# SensorMoteSMT_V1_1MCAD.net
KiCad netlist of a schematic drawn in EAGLE
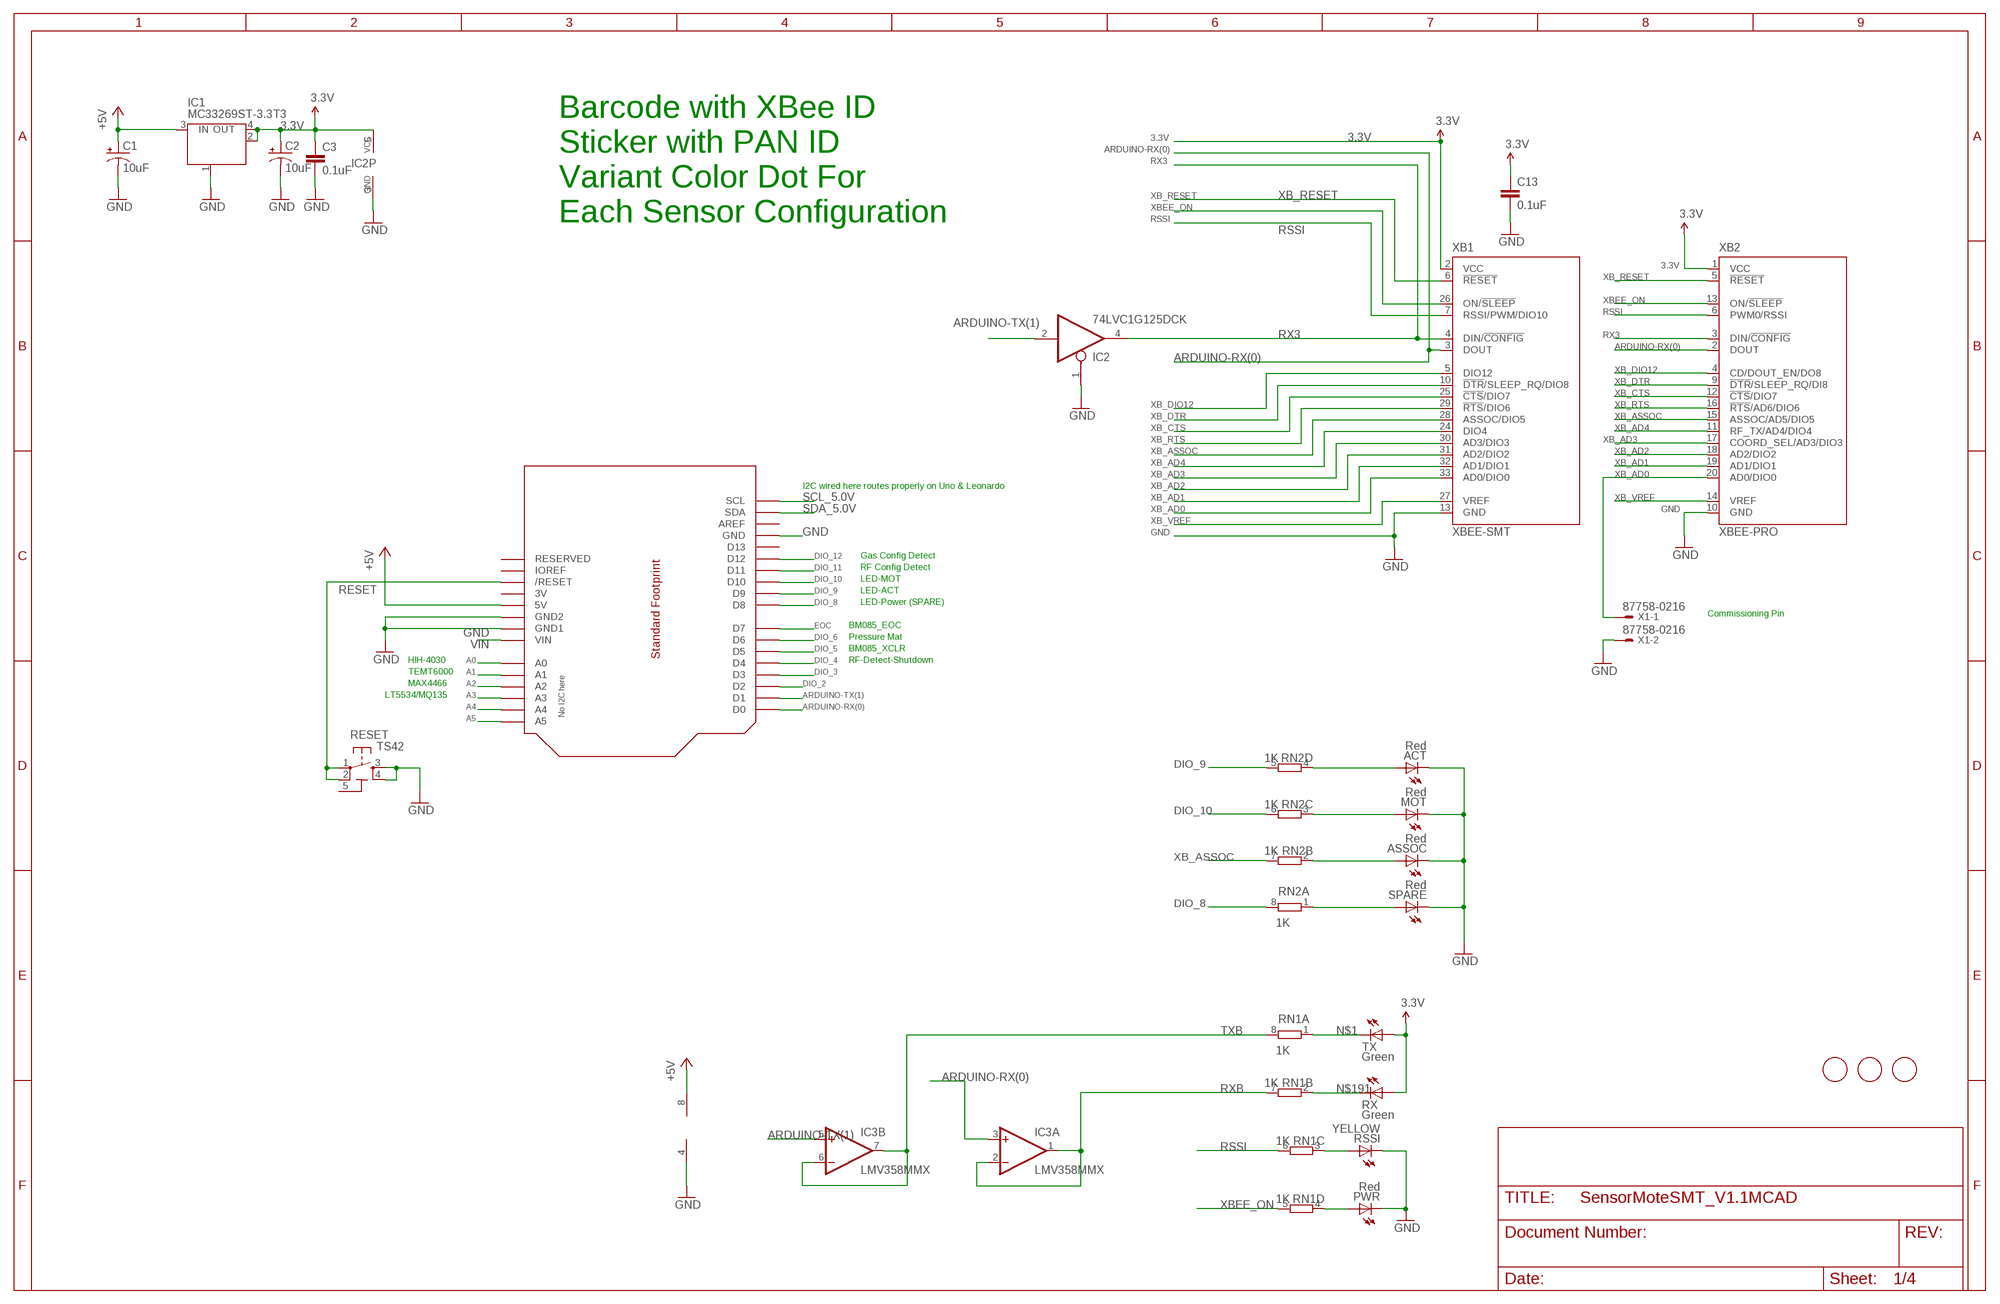
[diagram p0: schematic, sheet 1]
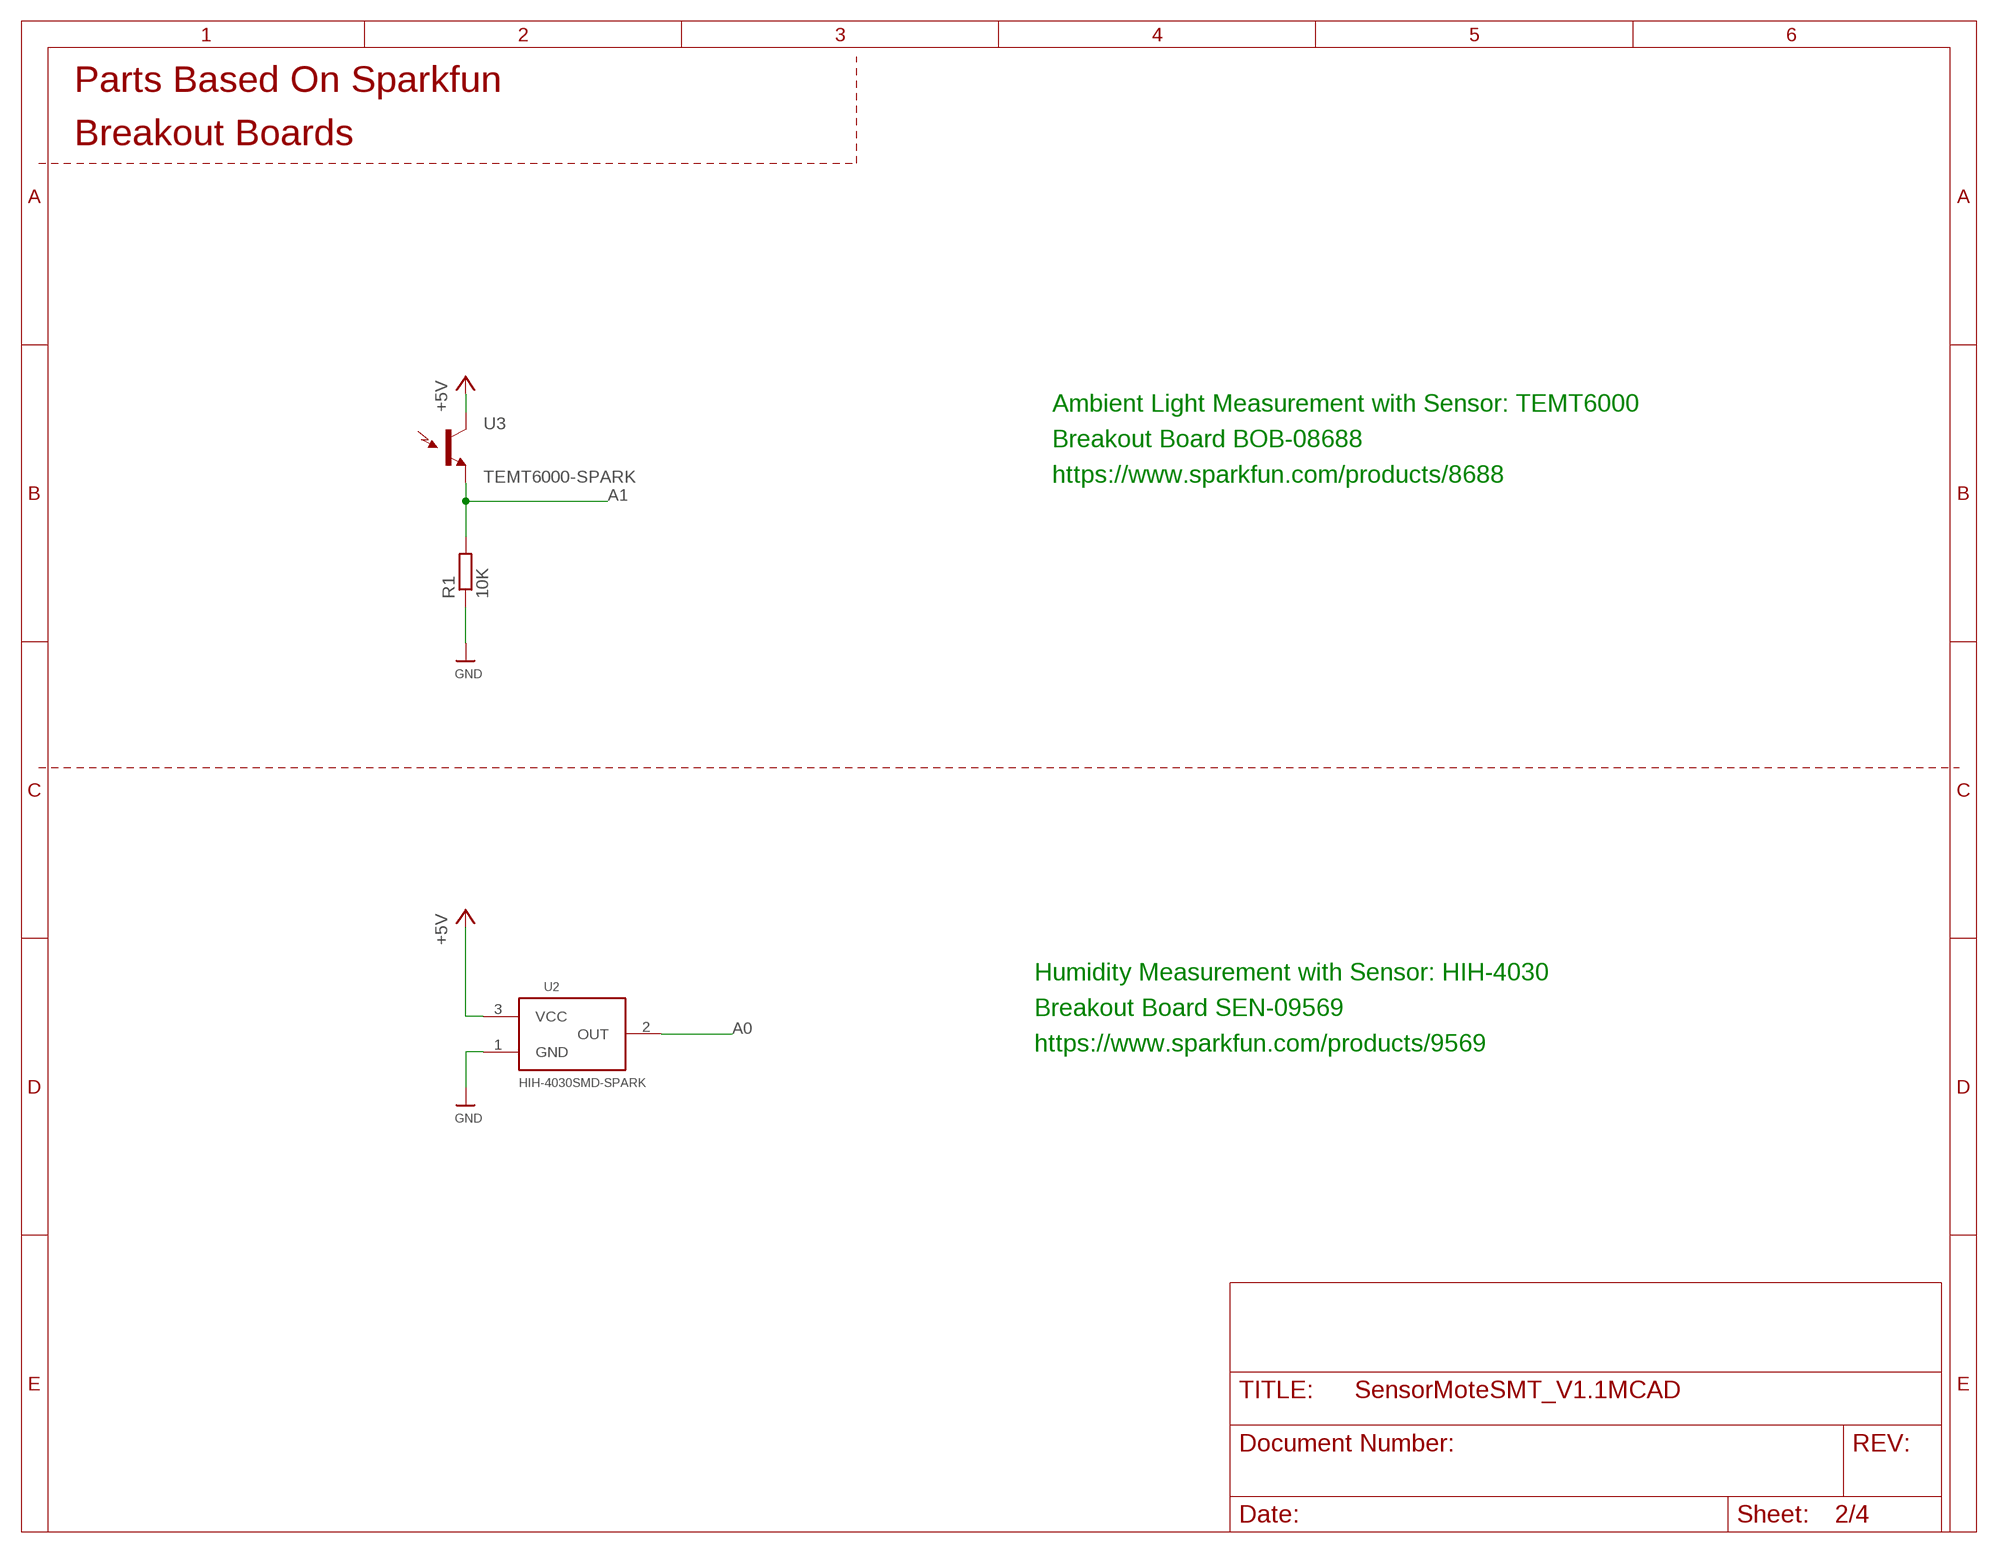
[diagram p1: schematic, sheet 2]
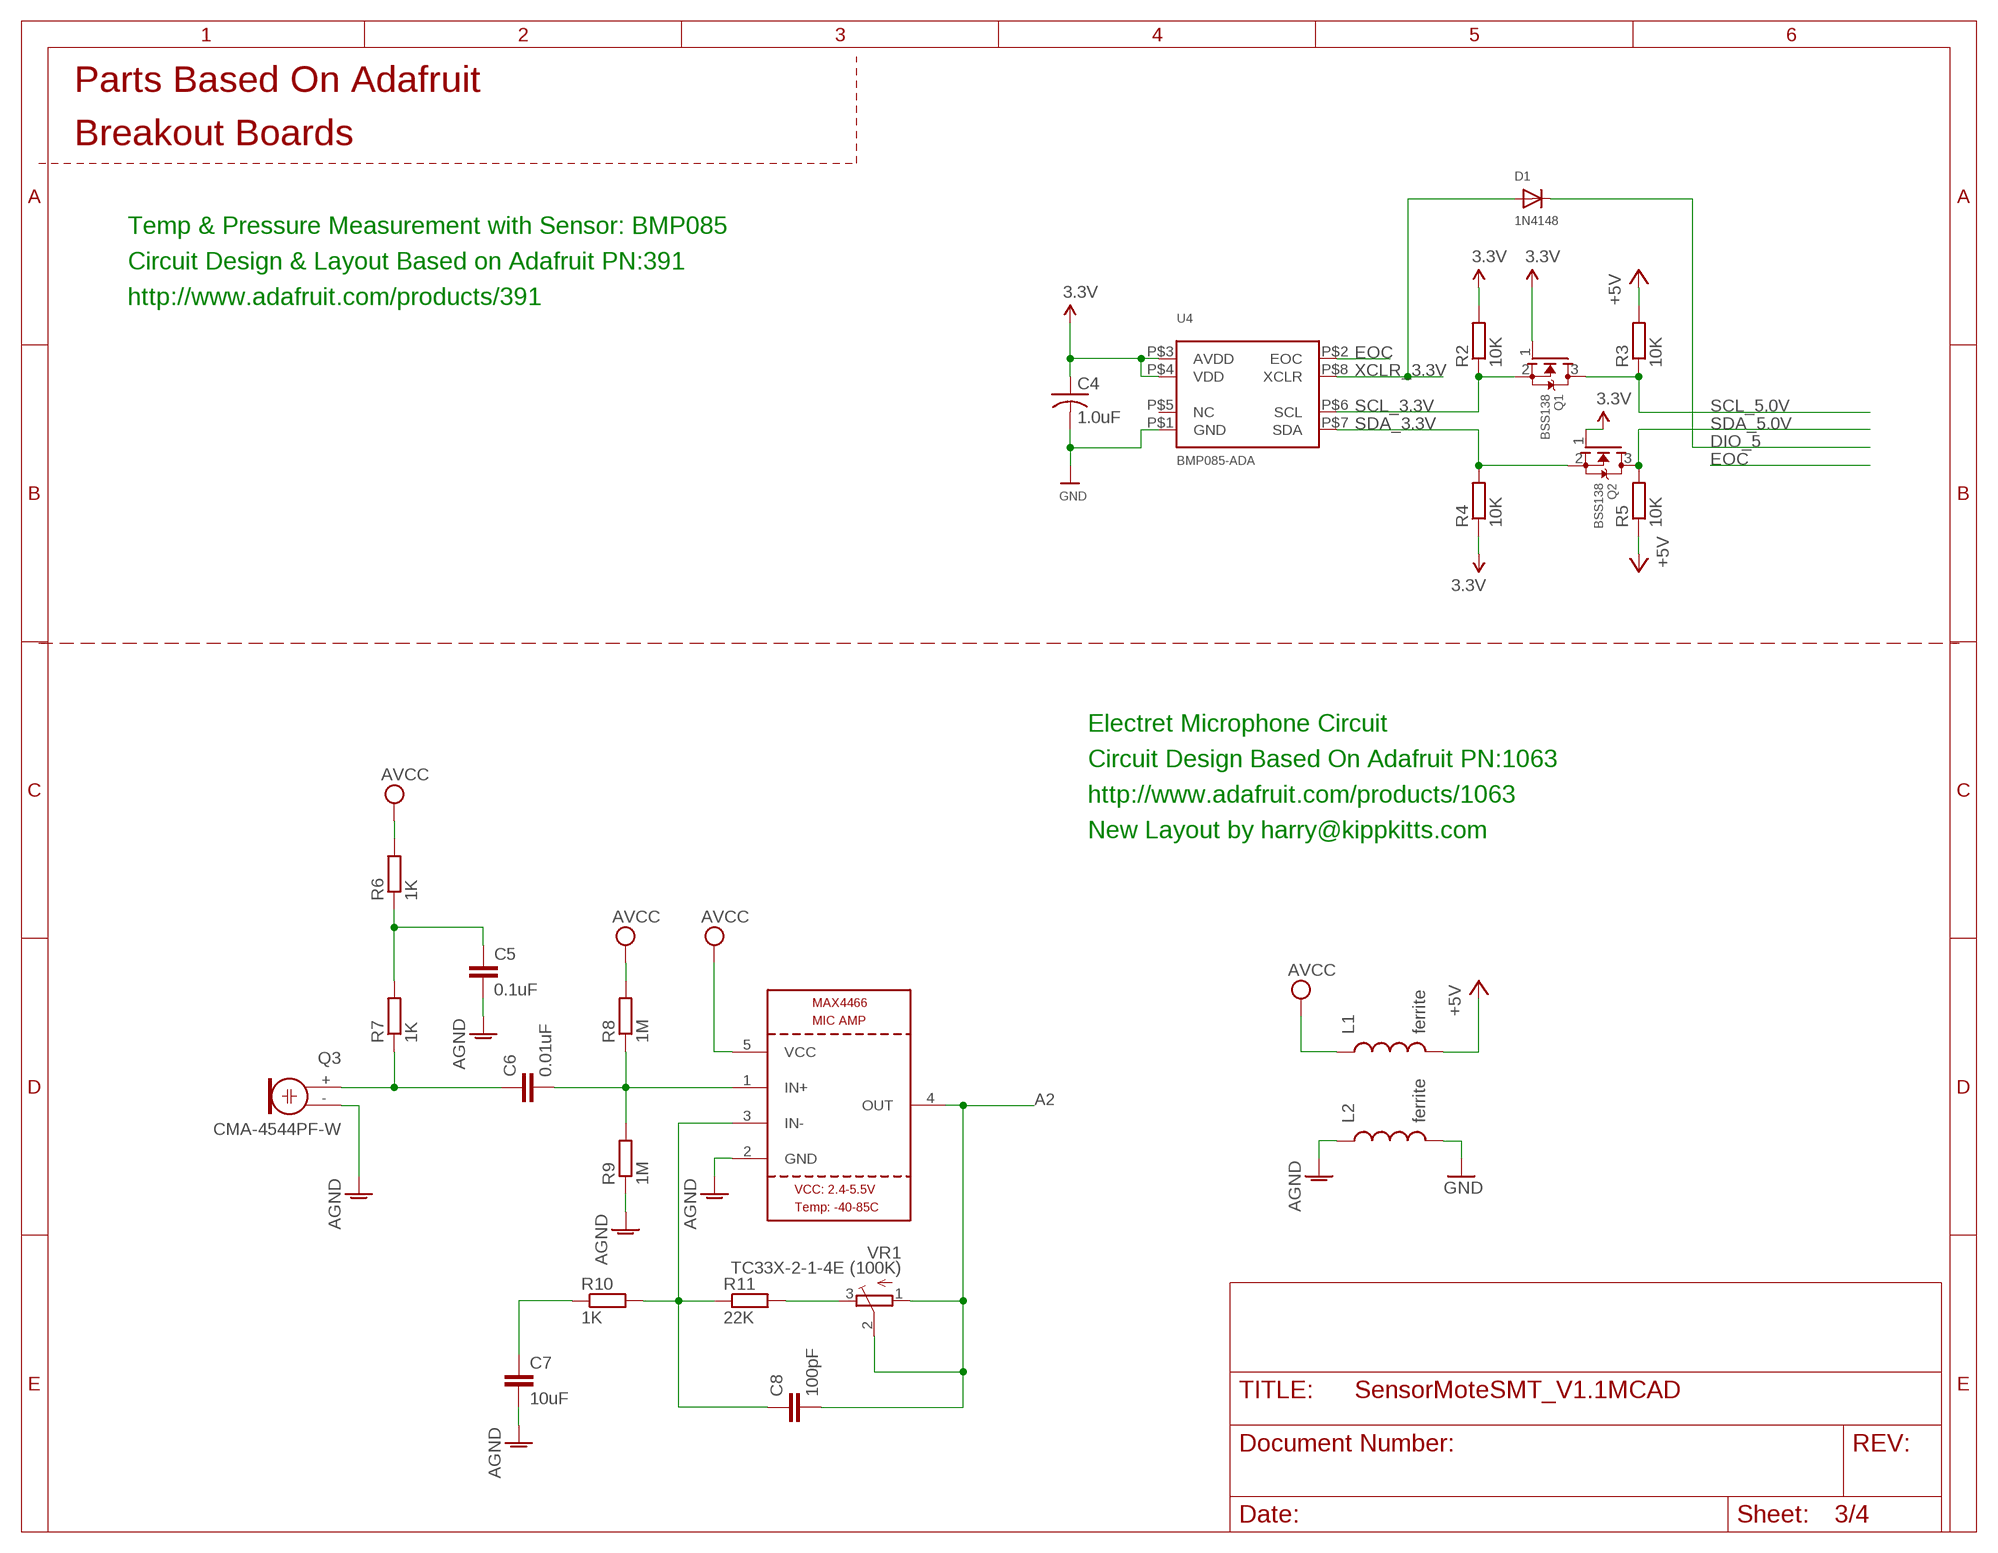
[diagram p2: schematic, sheet 3]
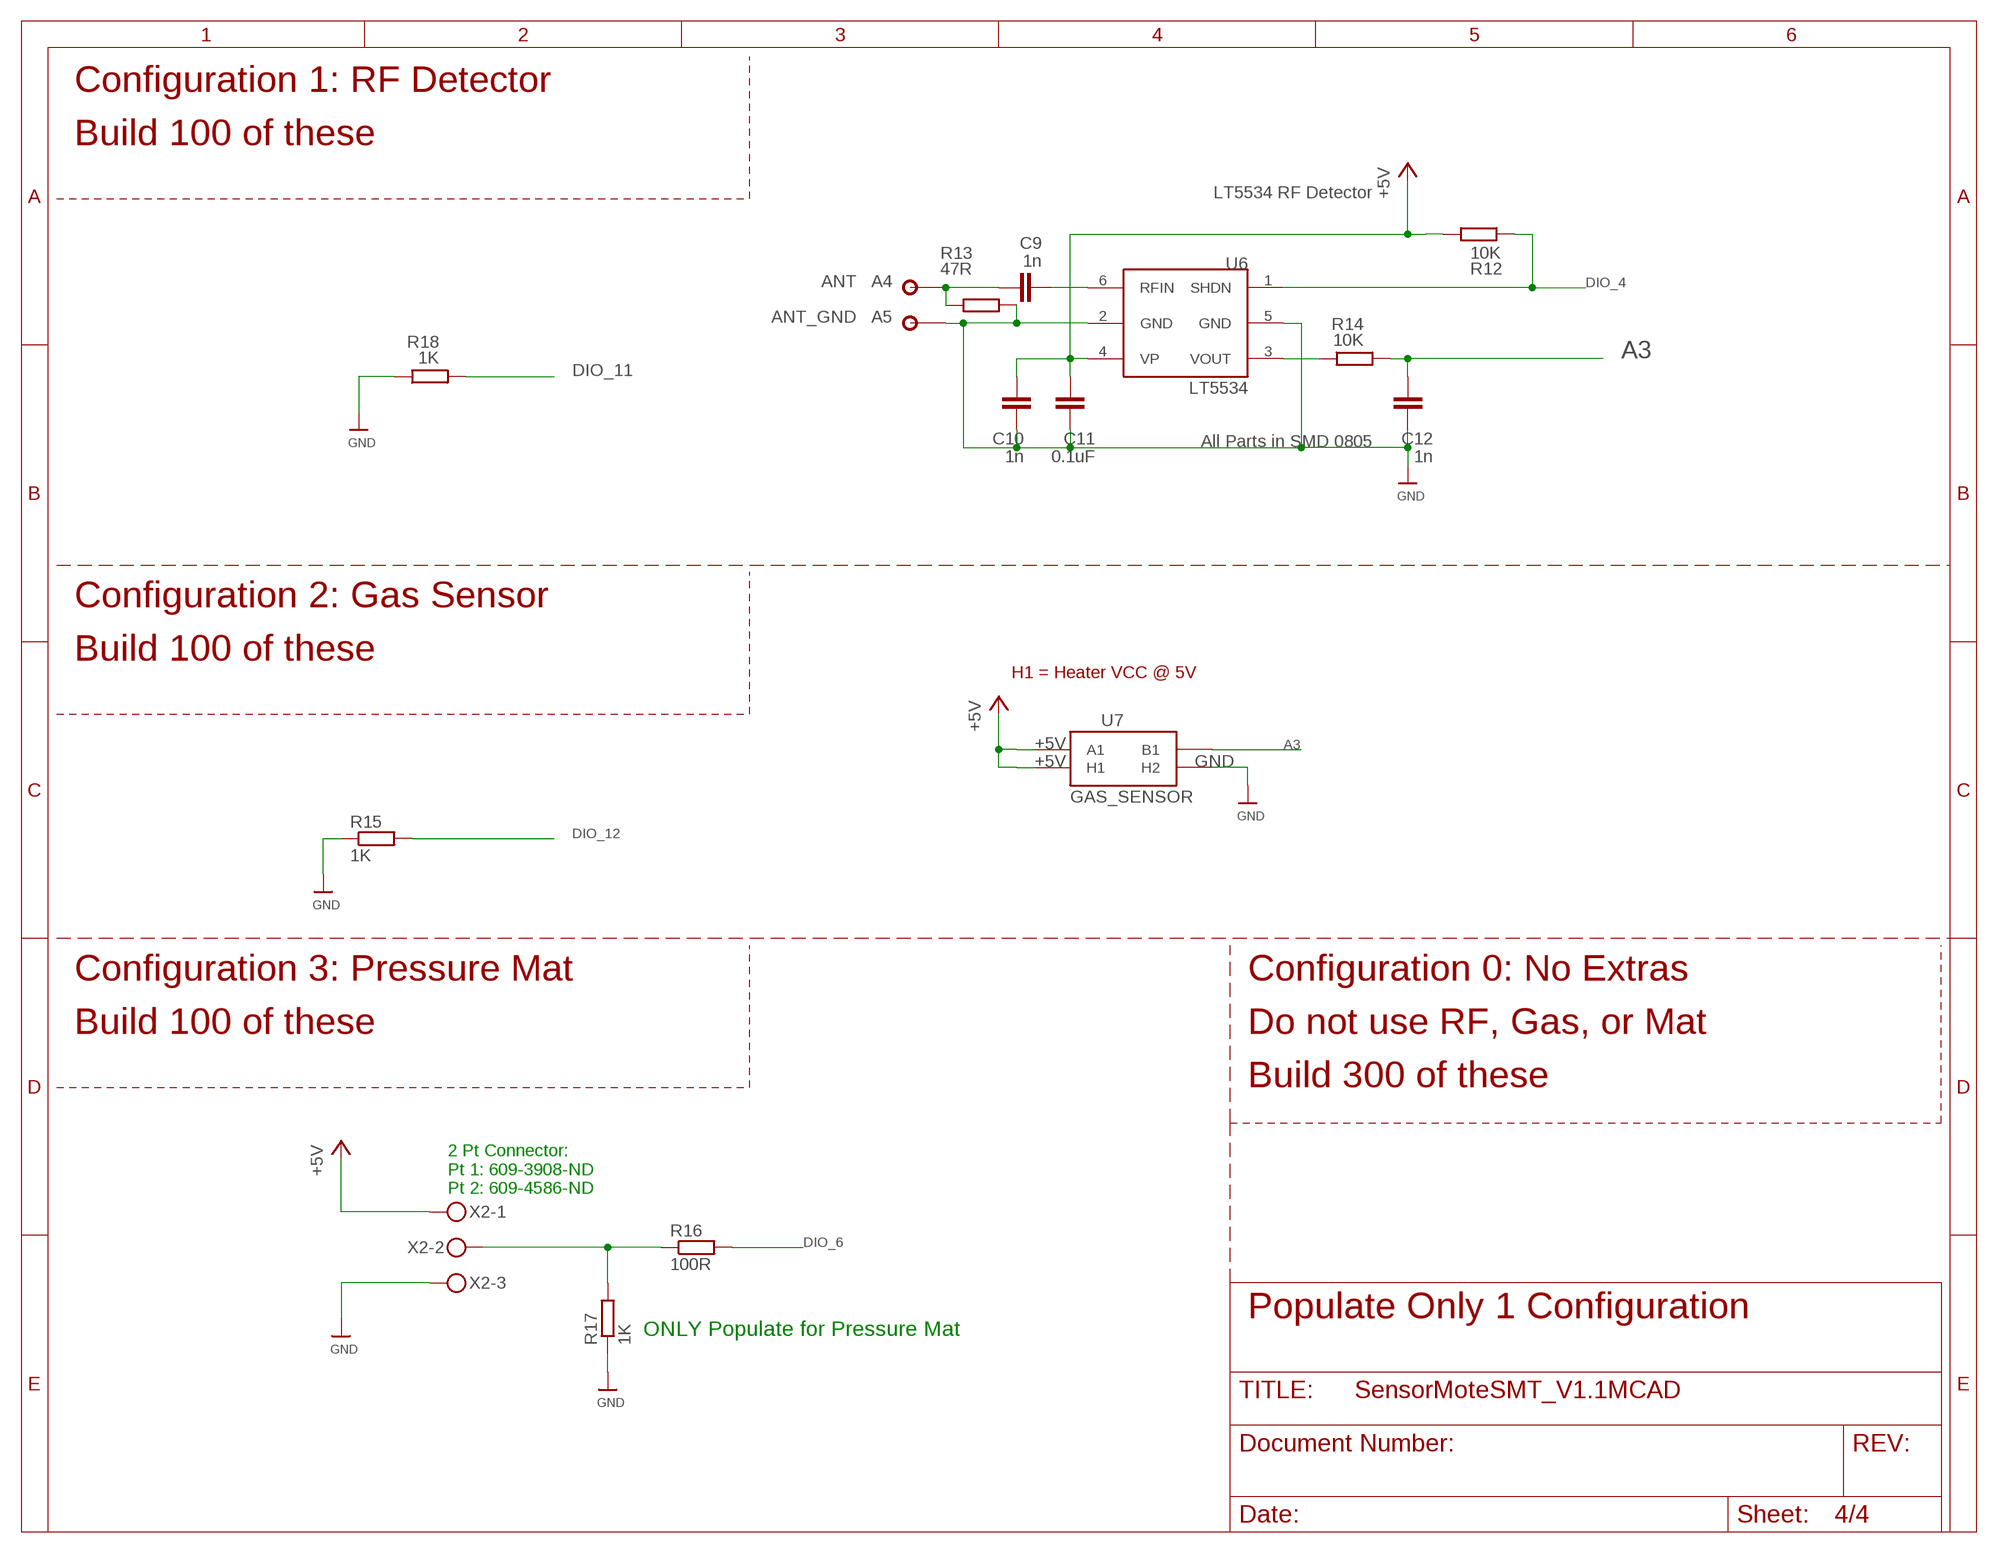
[diagram p3: schematic, sheet 4]

(export (version "E")
  (design (tool "Eeschema 10.0.6"))
  (components
    (comp (ref "C4")
      (value "1.0uF")
      (footprint "eagle-import:C0805K")
      (libsource (lib "eagle-import") (part "C-USC0805K"))
    )
    (comp (ref "C5")
      (value "0.1uF")
      (footprint "eagle-import:C0805K")
      (libsource (lib "eagle-import") (part "C-EUC0805K"))
    )
    (comp (ref "C6")
      (value "0.01uF")
      (footprint "eagle-import:C0805K")
      (libsource (lib "eagle-import") (part "C-EUC0805K"))
    )
    (comp (ref "C7")
      (value "10uF")
      (footprint "eagle-import:C0805K")
      (libsource (lib "eagle-import") (part "C-EUC0805K"))
    )
    (comp (ref "C8")
      (value "100pF")
      (footprint "eagle-import:C0805K")
      (libsource (lib "eagle-import") (part "C-EUC0805K"))
    )
    (comp (ref "D1")
      (value "1N4148")
      (footprint "eagle-import:SOD-323F")
      (libsource (lib "eagle-import") (part "DIODESOD-323F"))
    )
    (comp (ref "L1")
      (value "ferrite")
      (footprint "eagle-import:0603")
      (libsource (lib "eagle-import") (part "INDUCTOR0603"))
    )
    (comp (ref "L2")
      (value "ferrite")
      (footprint "eagle-import:0603")
      (libsource (lib "eagle-import") (part "INDUCTOR0603"))
    )
    (comp (ref "Q1")
      (value "BSS138")
      (footprint "eagle-import:SOT23")
      (libsource (lib "eagle-import") (part "MOSFET-NREFLOW"))
    )
    (comp (ref "Q2")
      (value "BSS138")
      (footprint "eagle-import:SOT23")
      (libsource (lib "eagle-import") (part "MOSFET-NREFLOW"))
    )
    (comp (ref "Q3")
      (value "CMA-4544PF-W")
      (footprint "eagle-import:9.7ELECTRET")
      (libsource (lib "eagle-import") (part "ELECTRET"))
    )
    (comp (ref "R2")
      (value "10K")
      (footprint "eagle-import:R0805")
      (libsource (lib "eagle-import") (part "resistor_R-EU_R0805"))
    )
    (comp (ref "R3")
      (value "10K")
      (footprint "eagle-import:R0805")
      (libsource (lib "eagle-import") (part "resistor_R-EU_R0805"))
    )
    (comp (ref "R4")
      (value "10K")
      (footprint "eagle-import:R0805")
      (libsource (lib "eagle-import") (part "resistor_R-EU_R0805"))
    )
    (comp (ref "R5")
      (value "10K")
      (footprint "eagle-import:R0805")
      (libsource (lib "eagle-import") (part "resistor_R-EU_R0805"))
    )
    (comp (ref "R6")
      (value "1K")
      (footprint "eagle-import:R0805")
      (libsource (lib "eagle-import") (part "resistor_R-EU_R0805"))
    )
    (comp (ref "R7")
      (value "1K")
      (footprint "eagle-import:R0805")
      (libsource (lib "eagle-import") (part "resistor_R-EU_R0805"))
    )
    (comp (ref "R8")
      (value "1M")
      (footprint "eagle-import:R0805")
      (libsource (lib "eagle-import") (part "resistor_R-EU_R0805"))
    )
    (comp (ref "R9")
      (value "1M")
      (footprint "eagle-import:R0805")
      (libsource (lib "eagle-import") (part "resistor_R-EU_R0805"))
    )
    (comp (ref "R10")
      (value "1K")
      (footprint "eagle-import:R0805")
      (libsource (lib "eagle-import") (part "resistor_R-EU_R0805"))
    )
    (comp (ref "R11")
      (value "22K")
      (footprint "eagle-import:R0805")
      (libsource (lib "eagle-import") (part "resistor_R-EU_R0805"))
    )
    (comp (ref "U4")
      (value "BMP085-ADA")
      (footprint "eagle-import:BMP085")
      (libsource (lib "eagle-import") (part "BMP085"))
    )
    (comp (ref "U5")
      (value "MAX4466SC70")
      (footprint "eagle-import:SC70-5L")
      (libsource (lib "eagle-import") (part "MAX4466SC70"))
    )
    (comp (ref "VR1")
      (value "TC33X-2-1-4E (100K)")
      (footprint "eagle-import:TC33X")
      (libsource (lib "eagle-import") (part "TRIMPOTTC33X"))
    )
    (comp (ref "A4")
      (value "ANT")
      (footprint "eagle-import:PAD146")
      (libsource (lib "eagle-import") (part "PAD1,46MM"))
    )
    (comp (ref "A5")
      (value "ANT_GND")
      (footprint "eagle-import:PAD146")
      (libsource (lib "eagle-import") (part "PAD1,46MM"))
    )
    (comp (ref "C9")
      (value "1n")
      (footprint "eagle-import:C0805K")
      (libsource (lib "eagle-import") (part "C-EUC0805K"))
    )
    (comp (ref "C10")
      (value "1n")
      (footprint "eagle-import:C0805K")
      (libsource (lib "eagle-import") (part "C-EUC0805K"))
    )
    (comp (ref "C11")
      (value "0.1uF")
      (footprint "eagle-import:C0805K")
      (libsource (lib "eagle-import") (part "C-EUC0805K"))
    )
    (comp (ref "C12")
      (value "1n")
      (footprint "eagle-import:C0805K")
      (libsource (lib "eagle-import") (part "C-EUC0805K"))
    )
    (comp (ref "R12")
      (value "10K")
      (footprint "eagle-import:R0805")
      (libsource (lib "eagle-import") (part "R-EU_R0805"))
    )
    (comp (ref "R13")
      (value "47R")
      (footprint "eagle-import:R0805")
      (libsource (lib "eagle-import") (part "R-EU_R0805"))
    )
    (comp (ref "R14")
      (value "10K")
      (footprint "eagle-import:R0805")
      (libsource (lib "eagle-import") (part "R-EU_R0805"))
    )
    (comp (ref "R15")
      (value "1K")
      (footprint "eagle-import:R0805")
      (libsource (lib "eagle-import") (part "R-EU_R0805"))
    )
    (comp (ref "R16")
      (value "100R")
      (footprint "eagle-import:R0805")
      (libsource (lib "eagle-import") (part "R-EU_R0805"))
    )
    (comp (ref "R17")
      (value "1K")
      (footprint "eagle-import:R0805")
      (libsource (lib "eagle-import") (part "R-EU_R0805"))
    )
    (comp (ref "R18")
      (value "1K")
      (footprint "eagle-import:R0805")
      (libsource (lib "eagle-import") (part "R-EU_R0805"))
    )
    (comp (ref "U6")
      (value "LT5534")
      (footprint "eagle-import:SC70")
      (libsource (lib "eagle-import") (part "LTC55"))
    )
    (comp (ref "U7")
      (value "GAS_SENSOR")
      (footprint "eagle-import:MQ-3")
      (libsource (lib "eagle-import") (part "GAS_SENSOR"))
    )
    (comp (ref "X2")
      (value "MKDSN1,5/3-5,08")
      (footprint "eagle-import:MKDSN1,5_3-5,08")
      (fields (field (name "MPN") "SMKDSN1,5/3-5,08"))
      (libsource (lib "eagle-import") (part "MKDSN1,5/3-5,08"))
    )
    (comp (ref "R1")
      (value "10K")
      (footprint "eagle-import:R0805")
      (libsource (lib "eagle-import") (part "resistor_R-EU_R0805"))
    )
    (comp (ref "U2")
      (value "HIH-4030SMD-SPARK")
      (footprint "eagle-import:HIH-4030")
      (libsource (lib "eagle-import") (part "HIH-4030SMD"))
    )
    (comp (ref "U3")
      (value "TEMT6000-SPARK")
      (footprint "eagle-import:TEMT6000-SEN")
      (libsource (lib "eagle-import") (part "TEMT6000"))
    )
    (comp (ref "A1")
      (value "FIDUCIALMOUNT")
      (footprint "eagle-import:FIDUCIA-MOUNT")
      (libsource (lib "eagle-import") (part "FIDUCIALMOUNT"))
    )
    (comp (ref "A2")
      (value "FIDUCIALMOUNT")
      (footprint "eagle-import:FIDUCIA-MOUNT")
      (libsource (lib "eagle-import") (part "FIDUCIALMOUNT"))
    )
    (comp (ref "A3")
      (value "FIDUCIALMOUNT")
      (footprint "eagle-import:FIDUCIA-MOUNT")
      (libsource (lib "eagle-import") (part "FIDUCIALMOUNT"))
    )
    (comp (ref "ACT")
      (value "Red")
      (footprint "eagle-import:CHIP-LED0805")
      (libsource (lib "eagle-import") (part "LEDCHIP-LED0805"))
    )
    (comp (ref "ASSOC")
      (value "Red")
      (footprint "eagle-import:CHIP-LED0805")
      (libsource (lib "eagle-import") (part "LEDCHIP-LED0805"))
    )
    (comp (ref "C1")
      (value "10uF")
      (footprint "eagle-import:EIA3216")
      (libsource (lib "eagle-import") (part "CAP_POL1206"))
    )
    (comp (ref "C2")
      (value "10uF")
      (footprint "eagle-import:EIA3216")
      (libsource (lib "eagle-import") (part "CAP_POL1206"))
    )
    (comp (ref "C3")
      (value "0.1uF")
      (footprint "eagle-import:C0805K")
      (libsource (lib "eagle-import") (part "C-EUC0805K"))
    )
    (comp (ref "C13")
      (value "0.1uF")
      (footprint "eagle-import:C0805K")
      (libsource (lib "eagle-import") (part "C-EUC0805K"))
    )
    (comp (ref "IC1")
      (value "MC33269ST-3.3T3")
      (footprint "eagle-import:SOT223")
      (libsource (lib "eagle-import") (part "MC33269ST-3.3T3"))
    )
    (comp (ref "IC2")
      (value "74LVC1G125DCK")
      (footprint "eagle-import:SC70-5")
      (libsource (lib "eagle-import") (part "741G125DCKLVC"))
    )
    (comp (ref "IC3")
      (value "LMV358MMX")
      (footprint "eagle-import:MSOP08")
      (libsource (lib "eagle-import") (part "LMV358?MMX"))
    )
    (comp (ref "MOT")
      (value "Red")
      (footprint "eagle-import:CHIP-LED0805")
      (libsource (lib "eagle-import") (part "LEDCHIP-LED0805"))
    )
    (comp (ref "PWR")
      (value "Red")
      (footprint "eagle-import:CHIP-LED0805")
      (libsource (lib "eagle-import") (part "LEDCHIP-LED0805"))
    )
    (comp (ref "RESET")
      (value "TS42")
      (footprint "eagle-import:TS42")
      (libsource (lib "eagle-import") (part "TS42"))
    )
    (comp (ref "RN1")
      (value "1K")
      (footprint "eagle-import:CAY16")
      (libsource (lib "eagle-import") (part "4R-NCAY16"))
    )
    (comp (ref "RN2")
      (value "1K")
      (footprint "eagle-import:CAY16")
      (fields (field (name "OC_FARNELL") "unknown") (field (name "OC_NEWARK") "unknown"))
      (libsource (lib "eagle-import") (part "4R-NCAY16"))
    )
    (comp (ref "RSSI")
      (value "YELLOW")
      (footprint "eagle-import:CHIP-LED0805")
      (libsource (lib "eagle-import") (part "LEDCHIP-LED0805"))
    )
    (comp (ref "RX")
      (value "Green")
      (footprint "eagle-import:CHIP-LED0805")
      (libsource (lib "eagle-import") (part "LEDCHIP-LED0805"))
    )
    (comp (ref "SPARE")
      (value "Red")
      (footprint "eagle-import:CHIP-LED0805")
      (libsource (lib "eagle-import") (part "LEDCHIP-LED0805"))
    )
    (comp (ref "TX")
      (value "Green")
      (footprint "eagle-import:CHIP-LED0805")
      (libsource (lib "eagle-import") (part "LEDCHIP-LED0805"))
    )
    (comp (ref "U1")
      (value "ARDUINOR3")
      (footprint "eagle-import:ARDUINOR3_EXTENDED")
      (libsource (lib "eagle-import") (part "ARDUINOR3"))
    )
    (comp (ref "X1")
      (value "87758-0216")
      (footprint "eagle-import:87758-0216")
      (libsource (lib "eagle-import") (part "87758-0216"))
    )
    (comp (ref "XB1")
      (value "XBEE-SMT")
      (footprint "eagle-import:XBEE-SMT")
      (libsource (lib "eagle-import") (part "XBEE-SMT"))
    )
    (comp (ref "XB2")
      (value "XBEE-PRO")
      (footprint "eagle-import:XBEE-PRO")
      (fields (field (name "MPN") "XBP24-AWI-001"))
      (libsource (lib "eagle-import") (part "XBEE-PRO"))
    )
  )
  (nets
    (net (code "1") (name "+5V") (class "Default")
      (node (ref "C1") (pin "A") (pinfunction "+_A") (pintype "passive"))
      (node (ref "C10") (pin "2") (pinfunction "2_2") (pintype "passive"))
      (node (ref "C11") (pin "2") (pinfunction "2_2") (pintype "passive"))
      (node (ref "IC1") (pin "3") (pinfunction "IN_3") (pintype "input"))
      (node (ref "IC3") (pin "8") (pinfunction "V+_8") (pintype "power_in"))
      (node (ref "L1") (pin "2") (pinfunction "2_2") (pintype "passive"))
      (node (ref "R12") (pin "2") (pinfunction "2_2") (pintype "passive"))
      (node (ref "R3") (pin "2") (pinfunction "2_2") (pintype "passive"))
      (node (ref "R5") (pin "1") (pinfunction "1_1") (pintype "passive"))
      (node (ref "U1") (pin "5V") (pinfunction "5V_5V") (pintype "power_in"))
      (node (ref "U2") (pin "3") (pinfunction "VCC_3") (pintype "bidirectional"))
      (node (ref "U3") (pin "COLLECTOR") (pinfunction "C1_COLLECTOR") (pintype "passive"))
      (node (ref "U6") (pin "4") (pinfunction "VP_4") (pintype "bidirectional"))
      (node (ref "U7") (pin "A1") (pinfunction "A1_A1") (pintype "bidirectional"))
      (node (ref "U7") (pin "HA") (pinfunction "H1_HA") (pintype "bidirectional"))
      (node (ref "X2") (pin "1") (pinfunction "KL_1") (pintype "passive"))
    )
    (net (code "2") (name "3.3V") (class "Default")
      (node (ref "C13") (pin "1") (pinfunction "1_1") (pintype "passive"))
      (node (ref "C2") (pin "A") (pinfunction "+_A") (pintype "passive"))
      (node (ref "C3") (pin "1") (pinfunction "1_1") (pintype "passive"))
      (node (ref "C4") (pin "1") (pinfunction "1_1") (pintype "passive"))
      (node (ref "IC1") (pin "2") (pinfunction "OUT_2") (pintype "passive"))
      (node (ref "IC1") (pin "4") (pinfunction "OUT_4") (pintype "passive"))
      (node (ref "IC2") (pin "5") (pinfunction "VCC_5") (pintype "power_in"))
      (node (ref "Q1") (pin "1") (pinfunction "G_1") (pintype "bidirectional"))
      (node (ref "Q2") (pin "1") (pinfunction "G_1") (pintype "bidirectional"))
      (node (ref "R2") (pin "2") (pinfunction "2_2") (pintype "passive"))
      (node (ref "R4") (pin "1") (pinfunction "1_1") (pintype "passive"))
      (node (ref "RX") (pin "A") (pinfunction "A_A") (pintype "passive"))
      (node (ref "TX") (pin "A") (pinfunction "A_A") (pintype "passive"))
      (node (ref "U4") (pin "P$3") (pinfunction "AVDD_P$3") (pintype "bidirectional"))
      (node (ref "U4") (pin "P$4") (pinfunction "VDD_P$4") (pintype "bidirectional"))
      (node (ref "XB1") (pin "2") (pinfunction "VCC_2") (pintype "power_in"))
      (node (ref "XB2") (pin "1") (pinfunction "VCC_1") (pintype "power_in"))
    )
    (net (code "3") (name "3V") (class "Default")
      (node (ref "U1") (pin "3V") (pinfunction "3V_3V") (pintype "power_in"))
    )
    (net (code "4") (name "5-GND") (class "Default")
      (node (ref "RESET") (pin "5") (pinfunction "5-GND_5") (pintype "power_in"))
    )
    (net (code "5") (name "A0") (class "Default")
      (node (ref "U1") (pin "A0") (pinfunction "A0_A0") (pintype "bidirectional"))
      (node (ref "U2") (pin "2") (pinfunction "OUT_2") (pintype "bidirectional"))
    )
    (net (code "6") (name "A1") (class "Default")
      (node (ref "R1") (pin "2") (pinfunction "2_2") (pintype "passive"))
      (node (ref "U1") (pin "A1") (pinfunction "A1_A1") (pintype "bidirectional"))
      (node (ref "U3") (pin "EMITTER") (pinfunction "E1_EMITTER") (pintype "passive"))
    )
    (net (code "7") (name "A2") (class "Default")
      (node (ref "C8") (pin "2") (pinfunction "2_2") (pintype "passive"))
      (node (ref "U1") (pin "A2") (pinfunction "A2_A2") (pintype "bidirectional"))
      (node (ref "U5") (pin "4") (pinfunction "OUT_4") (pintype "output"))
      (node (ref "VR1") (pin "1") (pinfunction "A_1") (pintype "passive"))
      (node (ref "VR1") (pin "2") (pinfunction "S_2") (pintype "passive"))
    )
    (net (code "8") (name "A3") (class "Default")
      (node (ref "C12") (pin "2") (pinfunction "2_2") (pintype "passive"))
      (node (ref "R14") (pin "2") (pinfunction "2_2") (pintype "passive"))
      (node (ref "U1") (pin "A3") (pinfunction "A3_A3") (pintype "bidirectional"))
      (node (ref "U7") (pin "B1") (pinfunction "B1_B1") (pintype "bidirectional"))
    )
    (net (code "9") (name "A4") (class "Default")
      (node (ref "U1") (pin "A4") (pinfunction "A4_A4") (pintype "bidirectional"))
    )
    (net (code "10") (name "A5") (class "Default")
      (node (ref "U1") (pin "A5") (pinfunction "A5_A5") (pintype "bidirectional"))
    )
    (net (code "11") (name "AGND") (class "Default")
      (node (ref "C5") (pin "2") (pinfunction "2_2") (pintype "passive"))
      (node (ref "C7") (pin "2") (pinfunction "2_2") (pintype "passive"))
      (node (ref "L2") (pin "1") (pinfunction "1_1") (pintype "passive"))
      (node (ref "Q3") (pin "-") (pinfunction "1_-") (pintype "passive"))
      (node (ref "R9") (pin "1") (pinfunction "1_1") (pintype "passive"))
      (node (ref "U5") (pin "2") (pinfunction "GND_2") (pintype "power_in"))
    )
    (net (code "12") (name "ARDUINO-RX(0)") (class "Default")
      (node (ref "IC3") (pin "3") (pinfunction "+IN_3") (pintype "input"))
      (node (ref "U1") (pin "D0") (pinfunction "D0_D0") (pintype "bidirectional"))
      (node (ref "XB1") (pin "3") (pinfunction "DOUT_3") (pintype "output"))
      (node (ref "XB2") (pin "2") (pinfunction "DOUT_2") (pintype "output"))
    )
    (net (code "13") (name "ARDUINO-TX(1)") (class "Default")
      (node (ref "IC2") (pin "2") (pinfunction "I_2") (pintype "input"))
      (node (ref "IC3") (pin "5") (pinfunction "+IN_5") (pintype "input"))
      (node (ref "U1") (pin "D1") (pinfunction "D1_D1") (pintype "bidirectional"))
    )
    (net (code "14") (name "DIO_2") (class "Default")
      (node (ref "U1") (pin "D2") (pinfunction "D2_D2") (pintype "bidirectional"))
    )
    (net (code "15") (name "DIO_3") (class "Default")
      (node (ref "U1") (pin "D3") (pinfunction "D3_D3") (pintype "bidirectional"))
    )
    (net (code "16") (name "DIO_4") (class "Default")
      (node (ref "R12") (pin "1") (pinfunction "1_1") (pintype "passive"))
      (node (ref "U1") (pin "D4") (pinfunction "D4_D4") (pintype "bidirectional"))
      (node (ref "U6") (pin "1") (pinfunction "SHDN_1") (pintype "bidirectional"))
    )
    (net (code "17") (name "DIO_5") (class "Default")
      (node (ref "D1") (pin "C") (pinfunction "C_C") (pintype "passive"))
      (node (ref "U1") (pin "D5") (pinfunction "D5_D5") (pintype "bidirectional"))
    )
    (net (code "18") (name "DIO_6") (class "Default")
      (node (ref "R16") (pin "2") (pinfunction "2_2") (pintype "passive"))
      (node (ref "U1") (pin "D6") (pinfunction "D6_D6") (pintype "bidirectional"))
    )
    (net (code "19") (name "DIO_8") (class "Default")
      (node (ref "RN2") (pin "8") (pinfunction "2_8") (pintype "passive"))
      (node (ref "U1") (pin "D8") (pinfunction "D8_D8") (pintype "bidirectional"))
    )
    (net (code "20") (name "DIO_9") (class "Default")
      (node (ref "RN2") (pin "5") (pinfunction "2_5") (pintype "passive"))
      (node (ref "U1") (pin "D9") (pinfunction "D9_D9") (pintype "bidirectional"))
    )
    (net (code "21") (name "DIO_10") (class "Default")
      (node (ref "RN2") (pin "6") (pinfunction "2_6") (pintype "passive"))
      (node (ref "U1") (pin "D10") (pinfunction "D10_D10") (pintype "bidirectional"))
    )
    (net (code "22") (name "DIO_11") (class "Default")
      (node (ref "R18") (pin "2") (pinfunction "2_2") (pintype "passive"))
      (node (ref "U1") (pin "D11") (pinfunction "D11_D11") (pintype "bidirectional"))
    )
    (net (code "23") (name "DIO_12") (class "Default")
      (node (ref "R15") (pin "2") (pinfunction "2_2") (pintype "passive"))
      (node (ref "U1") (pin "D12") (pinfunction "D12_D12") (pintype "bidirectional"))
    )
    (net (code "24") (name "EOC") (class "Default")
      (node (ref "U1") (pin "D7") (pinfunction "D7_D7") (pintype "bidirectional"))
      (node (ref "U4") (pin "P$2") (pinfunction "EOC_P$2") (pintype "bidirectional"))
    )
    (net (code "25") (name "GND") (class "Default")
      (node (ref "A5") (pin "1") (pinfunction "1_1") (pintype "passive"))
      (node (ref "ACT") (pin "C") (pinfunction "C_C") (pintype "passive"))
      (node (ref "ASSOC") (pin "C") (pinfunction "C_C") (pintype "passive"))
      (node (ref "C1") (pin "C") (pinfunction "-_C") (pintype "passive"))
      (node (ref "C10") (pin "1") (pinfunction "1_1") (pintype "passive"))
      (node (ref "C11") (pin "1") (pinfunction "1_1") (pintype "passive"))
      (node (ref "C12") (pin "1") (pinfunction "1_1") (pintype "passive"))
      (node (ref "C13") (pin "2") (pinfunction "2_2") (pintype "passive"))
      (node (ref "C2") (pin "C") (pinfunction "-_C") (pintype "passive"))
      (node (ref "C3") (pin "2") (pinfunction "2_2") (pintype "passive"))
      (node (ref "C4") (pin "2") (pinfunction "2_2") (pintype "passive"))
      (node (ref "IC1") (pin "1") (pinfunction "GND/ADJ_1") (pintype "input"))
      (node (ref "IC2") (pin "1") (pinfunction "OE_1") (pintype "input"))
      (node (ref "IC2") (pin "3") (pinfunction "GND_3") (pintype "power_in"))
      (node (ref "IC3") (pin "4") (pinfunction "V-_4") (pintype "power_in"))
      (node (ref "L2") (pin "2") (pinfunction "2_2") (pintype "passive"))
      (node (ref "MOT") (pin "C") (pinfunction "C_C") (pintype "passive"))
      (node (ref "PWR") (pin "C") (pinfunction "C_C") (pintype "passive"))
      (node (ref "R1") (pin "1") (pinfunction "1_1") (pintype "passive"))
      (node (ref "R13") (pin "2") (pinfunction "2_2") (pintype "passive"))
      (node (ref "R15") (pin "1") (pinfunction "1_1") (pintype "passive"))
      (node (ref "R17") (pin "1") (pinfunction "1_1") (pintype "passive"))
      (node (ref "R18") (pin "1") (pinfunction "1_1") (pintype "passive"))
      (node (ref "RESET") (pin "3") (pinfunction "3_3") (pintype "passive"))
      (node (ref "RESET") (pin "4") (pinfunction "4_4") (pintype "passive"))
      (node (ref "RSSI") (pin "C") (pinfunction "C_C") (pintype "passive"))
      (node (ref "SPARE") (pin "C") (pinfunction "C_C") (pintype "passive"))
      (node (ref "U1") (pin "GND") (pinfunction "GND_GND") (pintype "power_in"))
      (node (ref "U1") (pin "GND1") (pinfunction "GND1_GND1") (pintype "power_in"))
      (node (ref "U1") (pin "GND2") (pinfunction "GND2_GND2") (pintype "power_in"))
      (node (ref "U2") (pin "1") (pinfunction "GND_1") (pintype "bidirectional"))
      (node (ref "U4") (pin "P$1") (pinfunction "GND_P$1") (pintype "bidirectional"))
      (node (ref "U6") (pin "2") (pinfunction "GND_2") (pintype "power_in"))
      (node (ref "U6") (pin "5") (pinfunction "GND_5") (pintype "power_in"))
      (node (ref "U7") (pin "HB") (pinfunction "H2_HB") (pintype "bidirectional"))
      (node (ref "X1") (pin "2") (pinfunction "S_2") (pintype "passive"))
      (node (ref "X2") (pin "3") (pinfunction "KL_3") (pintype "passive"))
      (node (ref "XB1") (pin "13") (pinfunction "GND_13") (pintype "power_in"))
      (node (ref "XB2") (pin "10") (pinfunction "GND_10") (pintype "power_in"))
    )
    (net (code "26") (name "N$1") (class "Default")
      (node (ref "RN1") (pin "1") (pinfunction "1_1") (pintype "passive"))
      (node (ref "TX") (pin "C") (pinfunction "C_C") (pintype "passive"))
    )
    (net (code "27") (name "N$191") (class "Default")
      (node (ref "RN1") (pin "2") (pinfunction "1_2") (pintype "passive"))
      (node (ref "RX") (pin "C") (pinfunction "C_C") (pintype "passive"))
    )
    (net (code "28") (name "Net-(A4-Pad1)") (class "Default")
      (node (ref "A4") (pin "1") (pinfunction "1_1") (pintype "passive"))
      (node (ref "C9") (pin "2") (pinfunction "2_2") (pintype "passive"))
      (node (ref "R13") (pin "1") (pinfunction "1_1") (pintype "passive"))
    )
    (net (code "29") (name "Net-(C5-Pad1)") (class "Default")
      (node (ref "C5") (pin "1") (pinfunction "1_1") (pintype "passive"))
      (node (ref "R6") (pin "1") (pinfunction "1_1") (pintype "passive"))
      (node (ref "R7") (pin "2") (pinfunction "2_2") (pintype "passive"))
    )
    (net (code "30") (name "Net-(C7-Pad1)") (class "Default")
      (node (ref "C7") (pin "1") (pinfunction "1_1") (pintype "passive"))
      (node (ref "R10") (pin "1") (pinfunction "1_1") (pintype "passive"))
    )
    (net (code "31") (name "Net-(Q3-2)") (class "Default")
      (node (ref "C6") (pin "1") (pinfunction "1_1") (pintype "passive"))
      (node (ref "Q3") (pin "+") (pinfunction "2_+") (pintype "passive"))
      (node (ref "R7") (pin "1") (pinfunction "1_1") (pintype "passive"))
    )
    (net (code "32") (name "Net-(RN1C-1)") (class "Default")
      (node (ref "RN1") (pin "3") (pinfunction "1_3") (pintype "passive"))
      (node (ref "RSSI") (pin "A") (pinfunction "A_A") (pintype "passive"))
    )
    (net (code "33") (name "Net-(RN1D-1)") (class "Default")
      (node (ref "PWR") (pin "A") (pinfunction "A_A") (pintype "passive"))
      (node (ref "RN1") (pin "4") (pinfunction "1_4") (pintype "passive"))
    )
    (net (code "34") (name "Net-(RN2-Pad1)") (class "Default")
      (node (ref "RN2") (pin "1") (pinfunction "1_1") (pintype "passive"))
      (node (ref "SPARE") (pin "A") (pinfunction "A_A") (pintype "passive"))
    )
    (net (code "35") (name "Net-(RN2B-1)") (class "Default")
      (node (ref "ASSOC") (pin "A") (pinfunction "A_A") (pintype "passive"))
      (node (ref "RN2") (pin "2") (pinfunction "1_2") (pintype "passive"))
    )
    (net (code "36") (name "Net-(RN2C-1)") (class "Default")
      (node (ref "MOT") (pin "A") (pinfunction "A_A") (pintype "passive"))
      (node (ref "RN2") (pin "3") (pinfunction "1_3") (pintype "passive"))
    )
    (net (code "37") (name "Net-(RN2D-1)") (class "Default")
      (node (ref "ACT") (pin "A") (pinfunction "A_A") (pintype "passive"))
      (node (ref "RN2") (pin "4") (pinfunction "1_4") (pintype "passive"))
    )
    (net (code "38") (name "Net-(U5-IN+)") (class "Default")
      (node (ref "C6") (pin "2") (pinfunction "2_2") (pintype "passive"))
      (node (ref "R8") (pin "1") (pinfunction "1_1") (pintype "passive"))
      (node (ref "R9") (pin "2") (pinfunction "2_2") (pintype "passive"))
      (node (ref "U5") (pin "1") (pinfunction "IN+_1") (pintype "input"))
    )
    (net (code "39") (name "Net-(U5-IN-)") (class "Default")
      (node (ref "C8") (pin "1") (pinfunction "1_1") (pintype "passive"))
      (node (ref "R10") (pin "2") (pinfunction "2_2") (pintype "passive"))
      (node (ref "R11") (pin "1") (pinfunction "1_1") (pintype "passive"))
      (node (ref "U5") (pin "3") (pinfunction "IN-_3") (pintype "input"))
    )
    (net (code "40") (name "Net-(U6-RFIN)") (class "Default")
      (node (ref "C9") (pin "1") (pinfunction "1_1") (pintype "passive"))
      (node (ref "U6") (pin "6") (pinfunction "RFIN_6") (pintype "bidirectional"))
    )
    (net (code "41") (name "Net-(U6-VOUT)") (class "Default")
      (node (ref "R14") (pin "1") (pinfunction "1_1") (pintype "passive"))
      (node (ref "U6") (pin "3") (pinfunction "VOUT_3") (pintype "bidirectional"))
    )
    (net (code "42") (name "Net-(VR1-E)") (class "Default")
      (node (ref "R11") (pin "2") (pinfunction "2_2") (pintype "passive"))
      (node (ref "VR1") (pin "3") (pinfunction "E_3") (pintype "passive"))
    )
    (net (code "43") (name "Net-(X2B-KL)") (class "Default")
      (node (ref "R16") (pin "1") (pinfunction "1_1") (pintype "passive"))
      (node (ref "R17") (pin "2") (pinfunction "2_2") (pintype "passive"))
      (node (ref "X2") (pin "2") (pinfunction "KL_2") (pintype "passive"))
    )
    (net (code "44") (name "RESET") (class "Default")
      (node (ref "RESET") (pin "1") (pinfunction "1_1") (pintype "passive"))
      (node (ref "RESET") (pin "2") (pinfunction "2_2") (pintype "passive"))
      (node (ref "U1") (pin "RESET") (pinfunction "/RESET_RESET") (pintype "bidirectional"))
    )
    (net (code "45") (name "RSSI") (class "Default")
      (node (ref "RN1") (pin "6") (pinfunction "2_6") (pintype "passive"))
      (node (ref "XB1") (pin "7") (pinfunction "RSSI/PWM/DIO10_7") (pintype "output"))
      (node (ref "XB2") (pin "6") (pinfunction "PWM0/RSSI_6") (pintype "output"))
    )
    (net (code "46") (name "RX3") (class "Default")
      (node (ref "IC2") (pin "4") (pinfunction "O_4") (pintype "tri_state"))
      (node (ref "XB1") (pin "4") (pinfunction "DIN/~{CONFIG}_4") (pintype "input"))
      (node (ref "XB2") (pin "3") (pinfunction "DIN/~{CONFIG}_3") (pintype "input"))
    )
    (net (code "47") (name "RXB") (class "Default")
      (node (ref "IC3") (pin "1") (pinfunction "OUT_1") (pintype "output"))
      (node (ref "IC3") (pin "2") (pinfunction "-IN_2") (pintype "input"))
      (node (ref "RN1") (pin "7") (pinfunction "2_7") (pintype "passive"))
    )
    (net (code "48") (name "SCL_3.3V") (class "Default")
      (node (ref "Q1") (pin "2") (pinfunction "S_2") (pintype "bidirectional"))
      (node (ref "R2") (pin "1") (pinfunction "1_1") (pintype "passive"))
      (node (ref "U4") (pin "P$6") (pinfunction "SCL_P$6") (pintype "bidirectional"))
    )
    (net (code "49") (name "SCL_5.0V") (class "Default")
      (node (ref "Q1") (pin "3") (pinfunction "D_3") (pintype "bidirectional"))
      (node (ref "R3") (pin "1") (pinfunction "1_1") (pintype "passive"))
      (node (ref "U1") (pin "SCL") (pinfunction "SCL_SCL") (pintype "bidirectional"))
    )
    (net (code "50") (name "SDA_3.3V") (class "Default")
      (node (ref "Q2") (pin "2") (pinfunction "S_2") (pintype "bidirectional"))
      (node (ref "R4") (pin "2") (pinfunction "2_2") (pintype "passive"))
      (node (ref "U4") (pin "P$7") (pinfunction "SDA_P$7") (pintype "bidirectional"))
    )
    (net (code "51") (name "SDA_5.0V") (class "Default")
      (node (ref "Q2") (pin "3") (pinfunction "D_3") (pintype "bidirectional"))
      (node (ref "R5") (pin "2") (pinfunction "2_2") (pintype "passive"))
      (node (ref "U1") (pin "SDA") (pinfunction "SDA_SDA") (pintype "bidirectional"))
    )
    (net (code "52") (name "TXB") (class "Default")
      (node (ref "IC3") (pin "6") (pinfunction "-IN_6") (pintype "input"))
      (node (ref "IC3") (pin "7") (pinfunction "OUT_7") (pintype "output"))
      (node (ref "RN1") (pin "8") (pinfunction "2_8") (pintype "passive"))
    )
    (net (code "53") (name "VCC") (class "Default")
      (node (ref "L1") (pin "1") (pinfunction "1_1") (pintype "passive"))
      (node (ref "R6") (pin "2") (pinfunction "2_2") (pintype "passive"))
      (node (ref "R8") (pin "2") (pinfunction "2_2") (pintype "passive"))
      (node (ref "U5") (pin "5") (pinfunction "VCC_5") (pintype "power_in"))
    )
    (net (code "54") (name "VIN") (class "Default")
      (node (ref "U1") (pin "VIN") (pinfunction "VIN_VIN") (pintype "power_in"))
    )
    (net (code "55") (name "XBEE_ON") (class "Default")
      (node (ref "RN1") (pin "5") (pinfunction "2_5") (pintype "passive"))
      (node (ref "XB1") (pin "26") (pinfunction "ON/~{SLEEP}_26") (pintype "output"))
      (node (ref "XB2") (pin "13") (pinfunction "ON/~{SLEEP}_13") (pintype "output"))
    )
    (net (code "56") (name "XB_AD0") (class "Default")
      (node (ref "X1") (pin "1") (pinfunction "S_1") (pintype "passive"))
      (node (ref "XB1") (pin "33") (pinfunction "AD0/DIO0_33") (pintype "bidirectional"))
      (node (ref "XB2") (pin "20") (pinfunction "AD0/DIO0_20") (pintype "bidirectional"))
    )
    (net (code "57") (name "XB_AD1") (class "Default")
      (node (ref "XB1") (pin "32") (pinfunction "AD1/DIO1_32") (pintype "bidirectional"))
      (node (ref "XB2") (pin "19") (pinfunction "AD1/DIO1_19") (pintype "bidirectional"))
    )
    (net (code "58") (name "XB_AD2") (class "Default")
      (node (ref "XB1") (pin "31") (pinfunction "AD2/DIO2_31") (pintype "bidirectional"))
      (node (ref "XB2") (pin "18") (pinfunction "AD2/DIO2_18") (pintype "bidirectional"))
    )
    (net (code "59") (name "XB_AD3") (class "Default")
      (node (ref "XB1") (pin "30") (pinfunction "AD3/DIO3_30") (pintype "bidirectional"))
      (node (ref "XB2") (pin "17") (pinfunction "COORD_SEL/AD3/DIO3_17") (pintype "bidirectional"))
    )
    (net (code "60") (name "XB_AD4") (class "Default")
      (node (ref "XB1") (pin "24") (pinfunction "DIO4_24") (pintype "bidirectional"))
      (node (ref "XB2") (pin "11") (pinfunction "RF_TX/AD4/DIO4_11") (pintype "bidirectional"))
    )
    (net (code "61") (name "XB_ASSOC") (class "Default")
      (node (ref "RN2") (pin "7") (pinfunction "2_7") (pintype "passive"))
      (node (ref "XB1") (pin "28") (pinfunction "ASSOC/DIO5_28") (pintype "bidirectional"))
      (node (ref "XB2") (pin "15") (pinfunction "ASSOC/AD5/DIO5_15") (pintype "bidirectional"))
    )
    (net (code "62") (name "XB_CTS") (class "Default")
      (node (ref "XB1") (pin "25") (pinfunction "~{CTS}/DIO7_25") (pintype "bidirectional"))
      (node (ref "XB2") (pin "12") (pinfunction "~{CTS}/DIO7_12") (pintype "bidirectional"))
    )
    (net (code "63") (name "XB_DIO12") (class "Default")
      (node (ref "XB1") (pin "5") (pinfunction "DIO12_5") (pintype "bidirectional"))
      (node (ref "XB2") (pin "4") (pinfunction "CD/DOUT_EN/DO8_4") (pintype "output"))
    )
    (net (code "64") (name "XB_DTR") (class "Default")
      (node (ref "XB1") (pin "10") (pinfunction "~{DTR}/SLEEP_RQ/DIO8_10") (pintype "bidirectional"))
      (node (ref "XB2") (pin "9") (pinfunction "~{DTR}/SLEEP_RQ/DI8_9") (pintype "bidirectional"))
    )
    (net (code "65") (name "XB_RESET") (class "Default")
      (node (ref "XB1") (pin "6") (pinfunction "~{RESET}_6") (pintype "input"))
      (node (ref "XB2") (pin "5") (pinfunction "~{RESET}_5") (pintype "input"))
    )
    (net (code "66") (name "XB_RTS") (class "Default")
      (node (ref "XB1") (pin "29") (pinfunction "~{RTS}/DIO6_29") (pintype "bidirectional"))
      (node (ref "XB2") (pin "16") (pinfunction "~{RTS}/AD6/DIO6_16") (pintype "bidirectional"))
    )
    (net (code "67") (name "XB_VREF") (class "Default")
      (node (ref "XB1") (pin "27") (pinfunction "VREF_27") (pintype "input"))
      (node (ref "XB2") (pin "14") (pinfunction "VREF_14") (pintype "input"))
    )
    (net (code "68") (name "XCLR_3.3V") (class "Default")
      (node (ref "D1") (pin "A") (pinfunction "A_A") (pintype "passive"))
      (node (ref "U4") (pin "P$8") (pinfunction "XCLR_P$8") (pintype "bidirectional"))
    )
    (net (code "69") (name "unconnected-(U1-PadAREF)") (class "Default")
      (node (ref "U1") (pin "AREF") (pinfunction "AREF_AREF") (pintype "bidirectional"))
    )
    (net (code "70") (name "unconnected-(U1-PadD13)") (class "Default")
      (node (ref "U1") (pin "D13") (pinfunction "D13_D13") (pintype "bidirectional"))
    )
    (net (code "71") (name "unconnected-(U1-PadIOREF)") (class "Default")
      (node (ref "U1") (pin "IOREF") (pinfunction "IOREF_IOREF") (pintype "output"))
    )
    (net (code "72") (name "unconnected-(U1-PadRESERVED)") (class "Default")
      (node (ref "U1") (pin "RESERVED") (pinfunction "RESERVED_RESERVED") (pintype "no_connect"))
    )
    (net (code "73") (name "unconnected-(U4-NC-PadP$5)") (class "Default")
      (node (ref "U4") (pin "P$5") (pinfunction "NC_P$5") (pintype "bidirectional"))
    )
  )
)
